# Side_Short.net
KiCad netlist of a schematic drawn in EAGLE
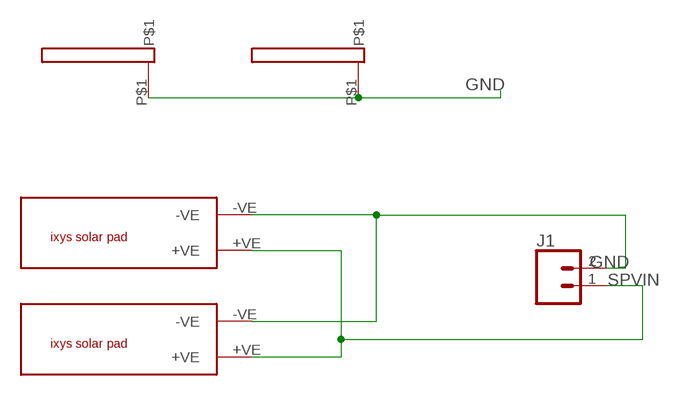
[diagram p0: schematic, sheet 1]

(export (version "E")
  (design (tool "Eeschema 10.0.6"))
  (components
    (comp (ref "J1")
      (value "CONN_02")
      (footprint "eagle-import:1X02")
      (libsource (lib "eagle-import") (part "CONN_02"))
    )
    (comp (ref "U$1")
      (value "IXYS")
      (footprint "eagle-import:IXYS")
      (libsource (lib "eagle-import") (part "IXYS"))
    )
    (comp (ref "U$2")
      (value "IXYS")
      (footprint "eagle-import:IXYS")
      (libsource (lib "eagle-import") (part "IXYS"))
    )
    (comp (ref "U$3")
      (value "16X2")
      (footprint "eagle-import:16X2")
      (libsource (lib "eagle-import") (part "16X2"))
    )
    (comp (ref "U$4")
      (value "16X2")
      (footprint "eagle-import:16X2")
      (libsource (lib "eagle-import") (part "16X2"))
    )
  )
  (nets
    (net (code "1") (name "/GND") (class "Default")
      (node (ref "J1") (pin "2") (pinfunction "2_2") (pintype "passive"))
      (node (ref "U$1") (pin "-VE") (pinfunction "-VE_-VE") (pintype "bidirectional"))
      (node (ref "U$2") (pin "-VE") (pinfunction "-VE_-VE") (pintype "bidirectional"))
      (node (ref "U$3") (pin "P$1") (pinfunction "P$1_P$1") (pintype "bidirectional"))
      (node (ref "U$4") (pin "P$1") (pinfunction "P$1_P$1") (pintype "bidirectional"))
    )
    (net (code "2") (name "/SPVIN") (class "Default")
      (node (ref "J1") (pin "1") (pinfunction "1_1") (pintype "passive"))
      (node (ref "U$1") (pin "+VE") (pinfunction "+VE_+VE") (pintype "bidirectional"))
      (node (ref "U$2") (pin "+VE") (pinfunction "+VE_+VE") (pintype "bidirectional"))
    )
  )
)
